# power_prong.net
KiCad netlist of a schematic drawn in EAGLE
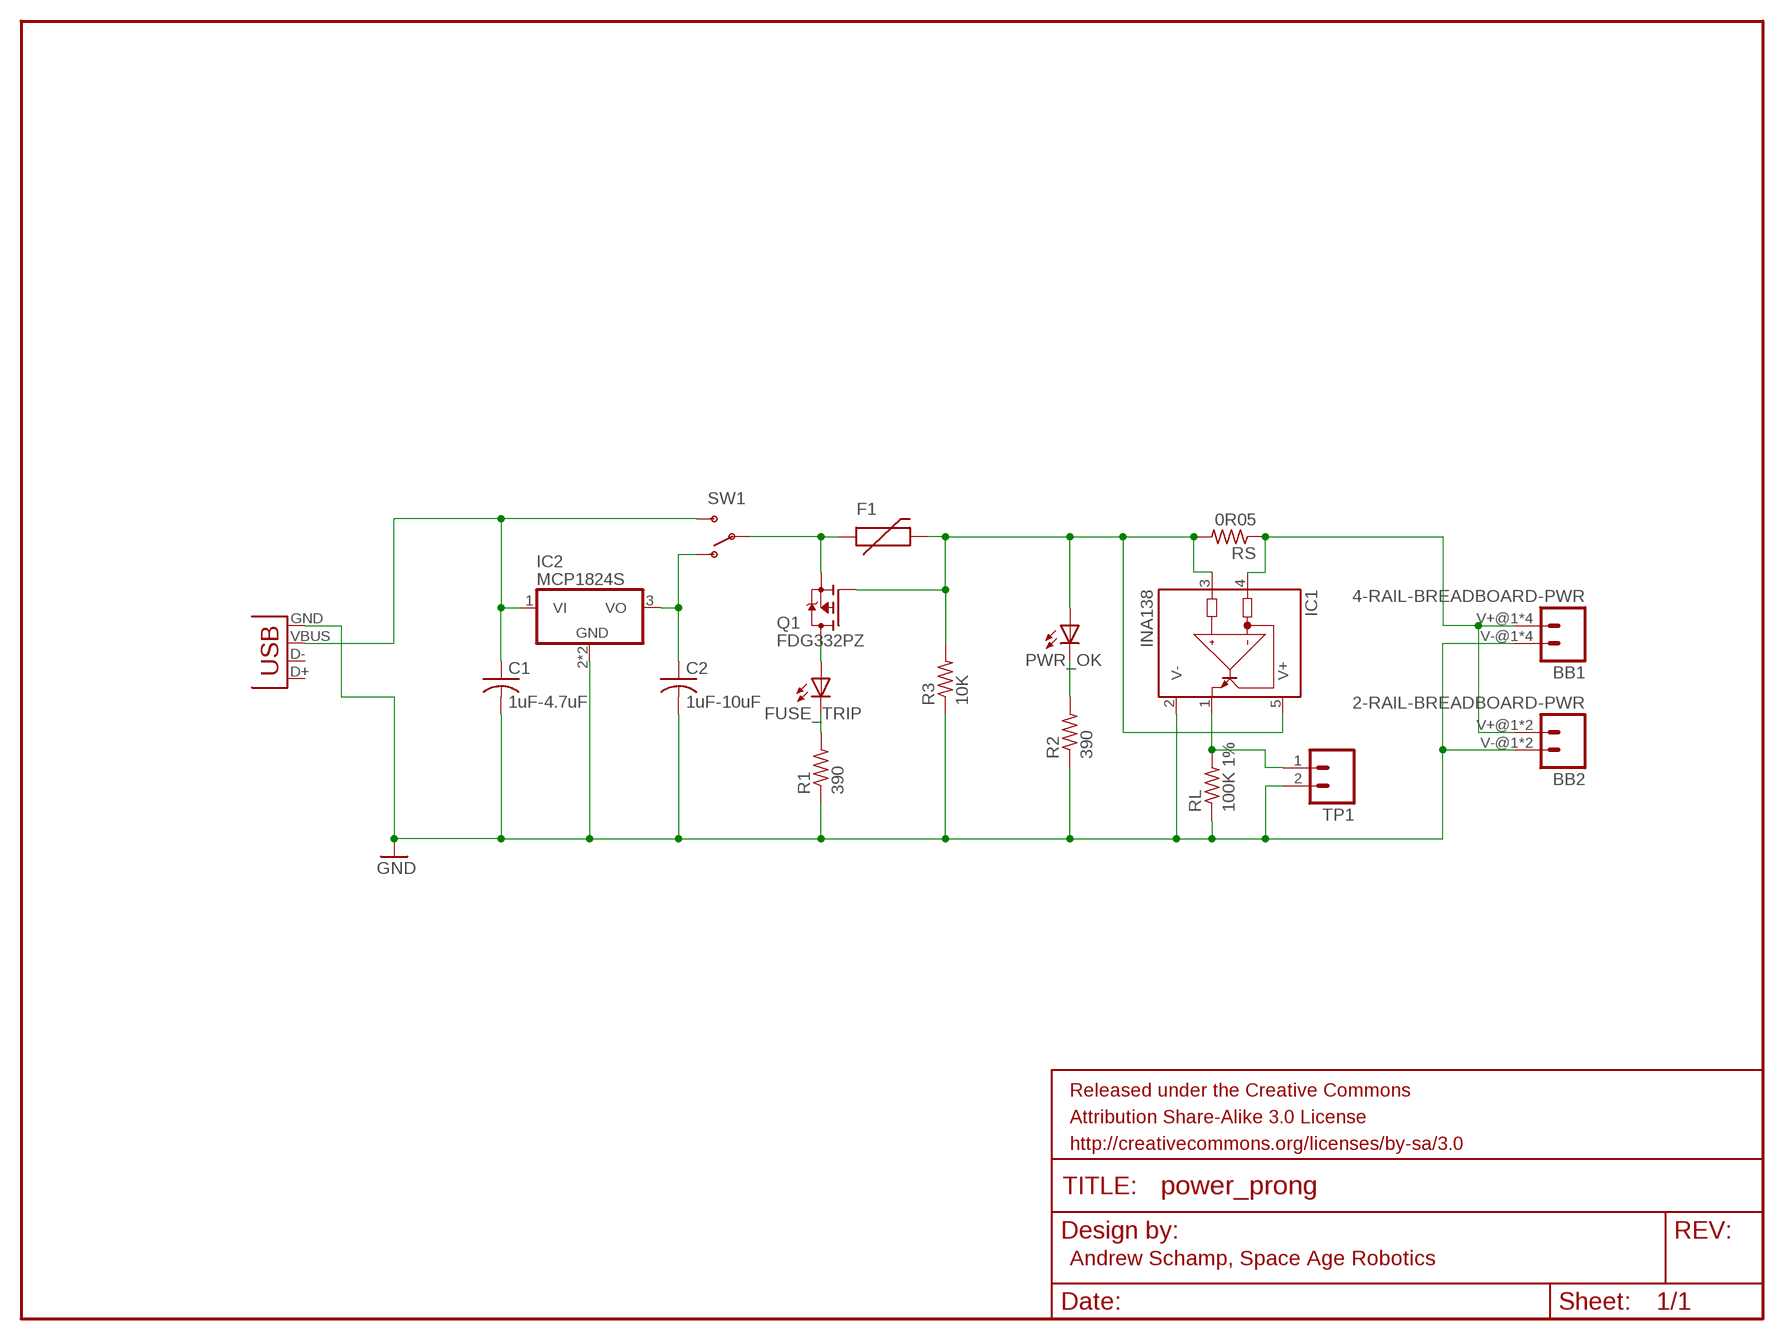
[diagram p0: schematic, sheet 1]

(export (version "E")
  (design (tool "Eeschema 10.0.6"))
  (components
    (comp (ref "BB1")
      (value "4-RAIL-BREADBOARD-PWR")
      (footprint "eagle-import:4-RAIL-BREADBOARD_X2")
      (libsource (lib "eagle-import") (part "4-RAIL-BREADBOARD-PWR"))
    )
    (comp (ref "BB2")
      (value "2-RAIL-BREADBOARD-PWR")
      (footprint "eagle-import:2-RAIL-BREADBOARD")
      (libsource (lib "eagle-import") (part "2-RAIL-BREADBOARD-PWR"))
    )
    (comp (ref "C1")
      (value "1uF-4.7uF")
      (footprint "eagle-import:C0805")
      (libsource (lib "eagle-import") (part "C-USC0805"))
    )
    (comp (ref "C2")
      (value "1uF-10uF")
      (footprint "eagle-import:C0805")
      (libsource (lib "eagle-import") (part "C-USC0805"))
    )
    (comp (ref "F1")
      (value "PTCSMD")
      (footprint "eagle-import:PTC-1206")
      (libsource (lib "eagle-import") (part "PTCSMD"))
    )
    (comp (ref "FUSE_TRIP")
      (value "LEDCHIP-LED0805")
      (footprint "eagle-import:CHIP-LED0805")
      (libsource (lib "eagle-import") (part "LEDCHIP-LED0805"))
    )
    (comp (ref "IC1")
      (value "INA138")
      (footprint "eagle-import:SOT23-5")
      (fields (field (name "MF") "TEXAS INSTRUMENTS") (field (name "MPN") "INA138NA/250"))
      (libsource (lib "eagle-import") (part "INA138"))
    )
    (comp (ref "IC2")
      (value "MCP1824S")
      (footprint "eagle-import:SOT223")
      (libsource (lib "eagle-import") (part "MCP1824S"))
    )
    (comp (ref "PWR_OK")
      (value "LEDCHIP-LED0805")
      (footprint "eagle-import:CHIP-LED0805")
      (libsource (lib "eagle-import") (part "LEDCHIP-LED0805"))
    )
    (comp (ref "Q1")
      (value "FDG332PZ")
      (footprint "eagle-import:SC70-6L")
      (libsource (lib "eagle-import") (part "FDG332PZ"))
    )
    (comp (ref "R1")
      (value "390")
      (footprint "eagle-import:R0603")
      (libsource (lib "eagle-import") (part "R-US_R0603"))
    )
    (comp (ref "R2")
      (value "390")
      (footprint "eagle-import:R0603")
      (libsource (lib "eagle-import") (part "R-US_R0603"))
    )
    (comp (ref "R3")
      (value "10K")
      (footprint "eagle-import:R0603")
      (libsource (lib "eagle-import") (part "R-US_R0603"))
    )
    (comp (ref "RL")
      (value "100K 1%")
      (footprint "eagle-import:R0805")
      (libsource (lib "eagle-import") (part "R-US_R0805"))
    )
    (comp (ref "RS")
      (value "0R05")
      (footprint "eagle-import:R0805")
      (libsource (lib "eagle-import") (part "R-US_R0805"))
    )
    (comp (ref "SW1")
      (value "SWITCH-SPDTMSH12204")
      (footprint "eagle-import:MSH12204")
      (libsource (lib "eagle-import") (part "SWITCH-SPDTMSH12204"))
    )
    (comp (ref "TP1")
      (value "M023.5MM-NO_SILK")
      (footprint "eagle-import:SCREWTERMINAL-3.5MM-2-NS")
      (libsource (lib "eagle-import") (part "M023.5MM-NO_SILK"))
    )
    (comp (ref "X1")
      (value "USBSMD")
      (footprint "eagle-import:USB-MINIB")
      (libsource (lib "eagle-import") (part "USBSMD"))
    )
  )
  (nets
    (net (code "1") (name "GND") (class "Default")
      (node (ref "BB1") (pin "V-@1") (pinfunction "2_V-@1") (pintype "passive"))
      (node (ref "BB1") (pin "V-@2") (pinfunction "2_V-@2") (pintype "passive"))
      (node (ref "BB1") (pin "V-@3") (pinfunction "2_V-@3") (pintype "passive"))
      (node (ref "BB1") (pin "V-@4") (pinfunction "2_V-@4") (pintype "passive"))
      (node (ref "BB2") (pin "V-@1") (pinfunction "2_V-@1") (pintype "passive"))
      (node (ref "BB2") (pin "V-@2") (pinfunction "2_V-@2") (pintype "passive"))
      (node (ref "C1") (pin "2") (pinfunction "2_2") (pintype "passive"))
      (node (ref "C2") (pin "2") (pinfunction "2_2") (pintype "passive"))
      (node (ref "IC1") (pin "2") (pinfunction "V-_2") (pintype "power_in"))
      (node (ref "IC2") (pin "2") (pinfunction "GND_2") (pintype "passive"))
      (node (ref "IC2") (pin "4") (pinfunction "GND_4") (pintype "passive"))
      (node (ref "R1") (pin "1") (pinfunction "1_1") (pintype "passive"))
      (node (ref "R2") (pin "1") (pinfunction "1_1") (pintype "passive"))
      (node (ref "R3") (pin "1") (pinfunction "1_1") (pintype "passive"))
      (node (ref "RL") (pin "1") (pinfunction "1_1") (pintype "passive"))
      (node (ref "TP1") (pin "2") (pinfunction "2_2") (pintype "passive"))
      (node (ref "X1") (pin "GND") (pinfunction "GND_GND") (pintype "bidirectional"))
    )
    (net (code "2") (name "Net-(FUSE_TRIP-PadA)") (class "Default")
      (node (ref "FUSE_TRIP") (pin "A") (pinfunction "A_A") (pintype "passive"))
      (node (ref "Q1") (pin "1") (pinfunction "D_1") (pintype "passive"))
      (node (ref "Q1") (pin "2") (pinfunction "D_2") (pintype "passive"))
      (node (ref "Q1") (pin "5") (pinfunction "D_5") (pintype "passive"))
      (node (ref "Q1") (pin "6") (pinfunction "D_6") (pintype "passive"))
    )
    (net (code "3") (name "Net-(FUSE_TRIP-PadC)") (class "Default")
      (node (ref "FUSE_TRIP") (pin "C") (pinfunction "C_C") (pintype "passive"))
      (node (ref "R1") (pin "2") (pinfunction "2_2") (pintype "passive"))
    )
    (net (code "4") (name "Net-(IC1-IN+)") (class "Default")
      (node (ref "F1") (pin "2") (pinfunction "2_2") (pintype "bidirectional"))
      (node (ref "IC1") (pin "3") (pinfunction "IN+_3") (pintype "input"))
      (node (ref "IC1") (pin "5") (pinfunction "V+_5") (pintype "power_in"))
      (node (ref "PWR_OK") (pin "A") (pinfunction "A_A") (pintype "passive"))
      (node (ref "Q1") (pin "3") (pinfunction "G_3") (pintype "passive"))
      (node (ref "R3") (pin "2") (pinfunction "2_2") (pintype "passive"))
      (node (ref "RS") (pin "2") (pinfunction "2_2") (pintype "passive"))
    )
    (net (code "5") (name "Net-(IC1-IN-)") (class "Default")
      (node (ref "BB1") (pin "V+@1") (pinfunction "1_V+@1") (pintype "passive"))
      (node (ref "BB1") (pin "V+@2") (pinfunction "1_V+@2") (pintype "passive"))
      (node (ref "BB1") (pin "V+@3") (pinfunction "1_V+@3") (pintype "passive"))
      (node (ref "BB1") (pin "V+@4") (pinfunction "1_V+@4") (pintype "passive"))
      (node (ref "BB2") (pin "V+@1") (pinfunction "1_V+@1") (pintype "passive"))
      (node (ref "BB2") (pin "V+@2") (pinfunction "1_V+@2") (pintype "passive"))
      (node (ref "IC1") (pin "4") (pinfunction "IN-_4") (pintype "input"))
      (node (ref "RS") (pin "1") (pinfunction "1_1") (pintype "passive"))
    )
    (net (code "6") (name "Net-(IC1-OUT)") (class "Default")
      (node (ref "IC1") (pin "1") (pinfunction "OUT_1") (pintype "output"))
      (node (ref "RL") (pin "2") (pinfunction "2_2") (pintype "passive"))
      (node (ref "TP1") (pin "1") (pinfunction "1_1") (pintype "passive"))
    )
    (net (code "7") (name "Net-(IC2-VI)") (class "Default")
      (node (ref "C1") (pin "1") (pinfunction "1_1") (pintype "passive"))
      (node (ref "IC2") (pin "1") (pinfunction "VI_1") (pintype "input"))
      (node (ref "SW1") (pin "3") (pinfunction "S_3") (pintype "passive"))
      (node (ref "X1") (pin "VBUS") (pinfunction "VBUS_VBUS") (pintype "bidirectional"))
    )
    (net (code "8") (name "Net-(IC2-VO)") (class "Default")
      (node (ref "C2") (pin "1") (pinfunction "1_1") (pintype "passive"))
      (node (ref "IC2") (pin "3") (pinfunction "VO_3") (pintype "passive"))
      (node (ref "SW1") (pin "1") (pinfunction "O_1") (pintype "passive"))
    )
    (net (code "9") (name "Net-(PWR_OK-PadC)") (class "Default")
      (node (ref "PWR_OK") (pin "C") (pinfunction "C_C") (pintype "passive"))
      (node (ref "R2") (pin "2") (pinfunction "2_2") (pintype "passive"))
    )
    (net (code "10") (name "Net-(Q1-S)") (class "Default")
      (node (ref "F1") (pin "1") (pinfunction "1_1") (pintype "bidirectional"))
      (node (ref "Q1") (pin "4") (pinfunction "S_4") (pintype "passive"))
      (node (ref "SW1") (pin "2") (pinfunction "P_2") (pintype "passive"))
    )
    (net (code "11") (name "unconnected-(X1-PadD+)") (class "Default")
      (node (ref "X1") (pin "D+") (pinfunction "D+_D+") (pintype "bidirectional"))
    )
    (net (code "12") (name "unconnected-(X1-PadD-)") (class "Default")
      (node (ref "X1") (pin "D-") (pinfunction "D-_D-") (pintype "bidirectional"))
    )
  )
)
